# expansion_board.net
KiCad netlist of a schematic drawn in EAGLE
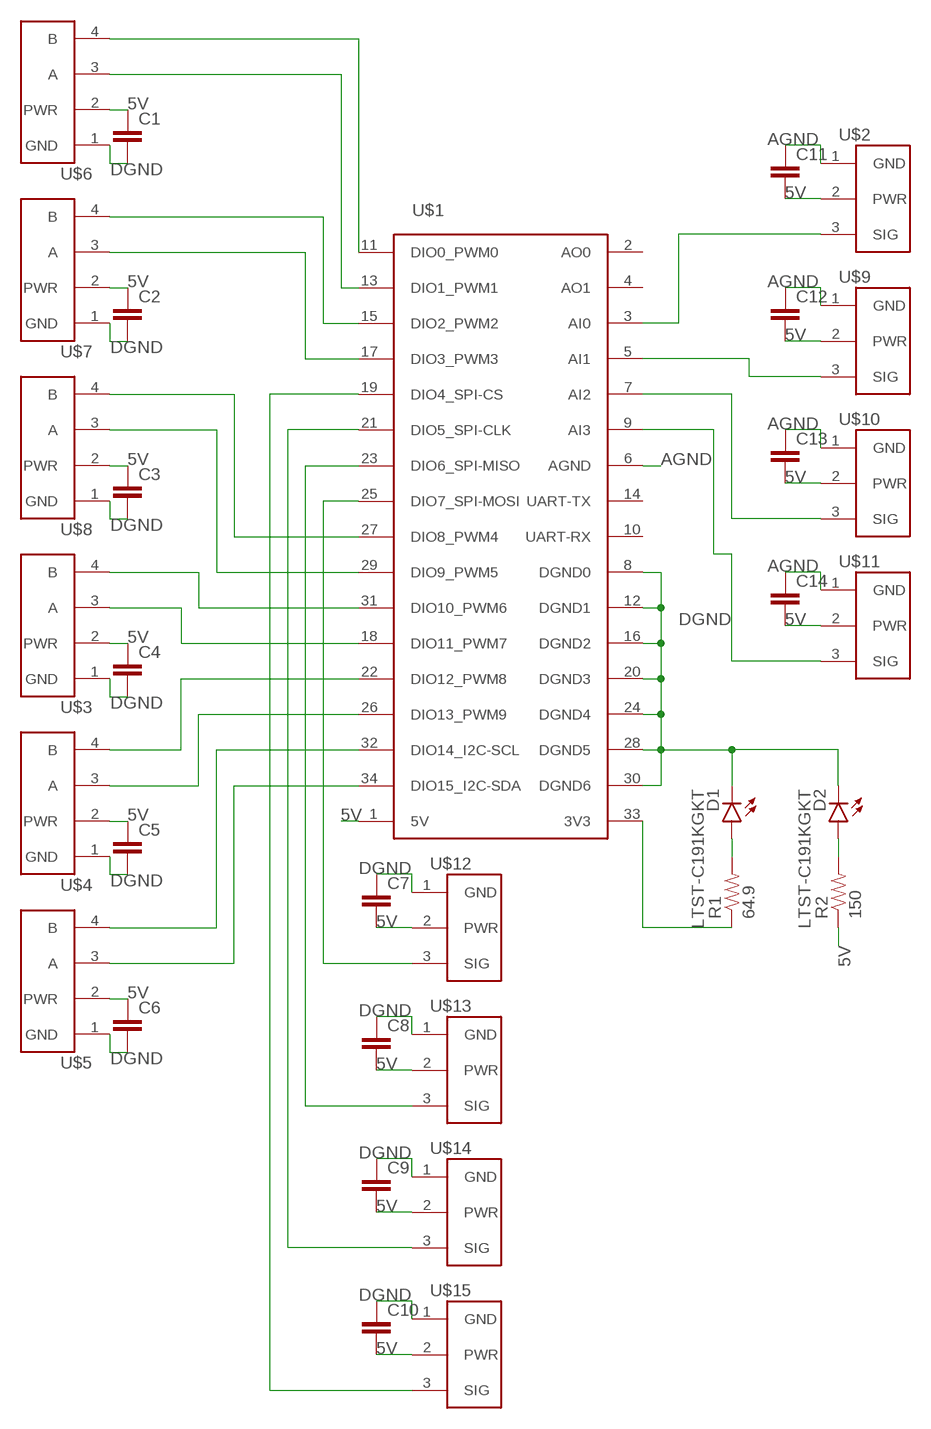
[diagram p0: schematic, sheet 1]

(export (version "E")
  (design (tool "Eeschema 10.0.6"))
  (components
    (comp (ref "C1")
      (value "CAP0603")
      (footprint "eagle-import:0603")
      (libsource (lib "eagle-import") (part "CAP0603"))
    )
    (comp (ref "C2")
      (value "CAP0603")
      (footprint "eagle-import:0603")
      (libsource (lib "eagle-import") (part "CAP0603"))
    )
    (comp (ref "C3")
      (value "CAP0603")
      (footprint "eagle-import:0603")
      (libsource (lib "eagle-import") (part "CAP0603"))
    )
    (comp (ref "C4")
      (value "CAP0603")
      (footprint "eagle-import:0603")
      (libsource (lib "eagle-import") (part "CAP0603"))
    )
    (comp (ref "C5")
      (value "CAP0603")
      (footprint "eagle-import:0603")
      (libsource (lib "eagle-import") (part "CAP0603"))
    )
    (comp (ref "C6")
      (value "CAP0603")
      (footprint "eagle-import:0603")
      (libsource (lib "eagle-import") (part "CAP0603"))
    )
    (comp (ref "C7")
      (value "CAP0603")
      (footprint "eagle-import:0603")
      (libsource (lib "eagle-import") (part "CAP0603"))
    )
    (comp (ref "C8")
      (value "CAP0603")
      (footprint "eagle-import:0603")
      (libsource (lib "eagle-import") (part "CAP0603"))
    )
    (comp (ref "C9")
      (value "CAP0603")
      (footprint "eagle-import:0603")
      (libsource (lib "eagle-import") (part "CAP0603"))
    )
    (comp (ref "C10")
      (value "CAP0603")
      (footprint "eagle-import:0603")
      (libsource (lib "eagle-import") (part "CAP0603"))
    )
    (comp (ref "C11")
      (value "CAP0603")
      (footprint "eagle-import:0603")
      (libsource (lib "eagle-import") (part "CAP0603"))
    )
    (comp (ref "C12")
      (value "CAP0603")
      (footprint "eagle-import:0603")
      (libsource (lib "eagle-import") (part "CAP0603"))
    )
    (comp (ref "C13")
      (value "CAP0603")
      (footprint "eagle-import:0603")
      (libsource (lib "eagle-import") (part "CAP0603"))
    )
    (comp (ref "C14")
      (value "CAP0603")
      (footprint "eagle-import:0603")
      (libsource (lib "eagle-import") (part "CAP0603"))
    )
    (comp (ref "D1")
      (value "LTST-C191KGKT")
      (footprint "eagle-import:LED-0603")
      (libsource (lib "eagle-import") (part "LED-GREEN0603"))
    )
    (comp (ref "D2")
      (value "LTST-C191KGKT")
      (footprint "eagle-import:LED-0603")
      (libsource (lib "eagle-import") (part "LED-GREEN0603"))
    )
    (comp (ref "R1")
      (value "64.9")
      (footprint "eagle-import:0603-RES")
      (libsource (lib "eagle-import") (part "RESISTOR0603-RES"))
    )
    (comp (ref "R2")
      (value "150")
      (footprint "eagle-import:0603-RES")
      (libsource (lib "eagle-import") (part "RESISTOR0603-RES"))
    )
    (comp (ref "U$1")
      (value "MXP")
      (footprint "eagle-import:SFH11-PBPC-D17-ST-BK")
      (libsource (lib "eagle-import") (part "MXP"))
    )
    (comp (ref "U$2")
      (value "22-23-2031")
      (footprint "eagle-import:22-23-2031")
      (libsource (lib "eagle-import") (part "22-23-2031"))
    )
    (comp (ref "U$3")
      (value "22-23-2041")
      (footprint "eagle-import:22-23-2041")
      (libsource (lib "eagle-import") (part "22-23-2041"))
    )
    (comp (ref "U$4")
      (value "22-23-2041")
      (footprint "eagle-import:22-23-2041")
      (libsource (lib "eagle-import") (part "22-23-2041"))
    )
    (comp (ref "U$5")
      (value "22-23-2041")
      (footprint "eagle-import:22-23-2041")
      (libsource (lib "eagle-import") (part "22-23-2041"))
    )
    (comp (ref "U$6")
      (value "22-23-2041")
      (footprint "eagle-import:22-23-2041")
      (libsource (lib "eagle-import") (part "22-23-2041"))
    )
    (comp (ref "U$7")
      (value "22-23-2041")
      (footprint "eagle-import:22-23-2041")
      (libsource (lib "eagle-import") (part "22-23-2041"))
    )
    (comp (ref "U$8")
      (value "22-23-2041")
      (footprint "eagle-import:22-23-2041")
      (libsource (lib "eagle-import") (part "22-23-2041"))
    )
    (comp (ref "U$9")
      (value "22-23-2031")
      (footprint "eagle-import:22-23-2031")
      (libsource (lib "eagle-import") (part "22-23-2031"))
    )
    (comp (ref "U$10")
      (value "22-23-2031")
      (footprint "eagle-import:22-23-2031")
      (libsource (lib "eagle-import") (part "22-23-2031"))
    )
    (comp (ref "U$11")
      (value "22-23-2031")
      (footprint "eagle-import:22-23-2031")
      (libsource (lib "eagle-import") (part "22-23-2031"))
    )
    (comp (ref "U$12")
      (value "22-23-2031")
      (footprint "eagle-import:22-23-2031")
      (libsource (lib "eagle-import") (part "22-23-2031"))
    )
    (comp (ref "U$13")
      (value "22-23-2031")
      (footprint "eagle-import:22-23-2031")
      (libsource (lib "eagle-import") (part "22-23-2031"))
    )
    (comp (ref "U$14")
      (value "22-23-2031")
      (footprint "eagle-import:22-23-2031")
      (libsource (lib "eagle-import") (part "22-23-2031"))
    )
    (comp (ref "U$15")
      (value "22-23-2031")
      (footprint "eagle-import:22-23-2031")
      (libsource (lib "eagle-import") (part "22-23-2031"))
    )
  )
  (nets
    (net (code "1") (name "/5V") (class "Default")
      (node (ref "C1") (pin "1") (pinfunction "1_1") (pintype "passive"))
      (node (ref "C10") (pin "2") (pinfunction "2_2") (pintype "passive"))
      (node (ref "C11") (pin "2") (pinfunction "2_2") (pintype "passive"))
      (node (ref "C12") (pin "2") (pinfunction "2_2") (pintype "passive"))
      (node (ref "C13") (pin "2") (pinfunction "2_2") (pintype "passive"))
      (node (ref "C14") (pin "2") (pinfunction "2_2") (pintype "passive"))
      (node (ref "C2") (pin "1") (pinfunction "1_1") (pintype "passive"))
      (node (ref "C3") (pin "1") (pinfunction "1_1") (pintype "passive"))
      (node (ref "C4") (pin "1") (pinfunction "1_1") (pintype "passive"))
      (node (ref "C5") (pin "1") (pinfunction "1_1") (pintype "passive"))
      (node (ref "C6") (pin "1") (pinfunction "1_1") (pintype "passive"))
      (node (ref "C7") (pin "2") (pinfunction "2_2") (pintype "passive"))
      (node (ref "C8") (pin "2") (pinfunction "2_2") (pintype "passive"))
      (node (ref "C9") (pin "2") (pinfunction "2_2") (pintype "passive"))
      (node (ref "R2") (pin "1") (pinfunction "1_1") (pintype "passive"))
      (node (ref "U$1") (pin "1") (pinfunction "5V_1") (pintype "power_in"))
      (node (ref "U$10") (pin "2") (pinfunction "PWR_2") (pintype "power_in"))
      (node (ref "U$11") (pin "2") (pinfunction "PWR_2") (pintype "power_in"))
      (node (ref "U$12") (pin "2") (pinfunction "PWR_2") (pintype "power_in"))
      (node (ref "U$13") (pin "2") (pinfunction "PWR_2") (pintype "power_in"))
      (node (ref "U$14") (pin "2") (pinfunction "PWR_2") (pintype "power_in"))
      (node (ref "U$15") (pin "2") (pinfunction "PWR_2") (pintype "power_in"))
      (node (ref "U$2") (pin "2") (pinfunction "PWR_2") (pintype "power_in"))
      (node (ref "U$3") (pin "2") (pinfunction "PWR_2") (pintype "power_in"))
      (node (ref "U$4") (pin "2") (pinfunction "PWR_2") (pintype "power_in"))
      (node (ref "U$5") (pin "2") (pinfunction "PWR_2") (pintype "power_in"))
      (node (ref "U$6") (pin "2") (pinfunction "PWR_2") (pintype "power_in"))
      (node (ref "U$7") (pin "2") (pinfunction "PWR_2") (pintype "power_in"))
      (node (ref "U$8") (pin "2") (pinfunction "PWR_2") (pintype "power_in"))
      (node (ref "U$9") (pin "2") (pinfunction "PWR_2") (pintype "power_in"))
    )
    (net (code "2") (name "/AGND") (class "Default")
      (node (ref "C11") (pin "1") (pinfunction "1_1") (pintype "passive"))
      (node (ref "C12") (pin "1") (pinfunction "1_1") (pintype "passive"))
      (node (ref "C13") (pin "1") (pinfunction "1_1") (pintype "passive"))
      (node (ref "C14") (pin "1") (pinfunction "1_1") (pintype "passive"))
      (node (ref "U$1") (pin "6") (pinfunction "AGND_6") (pintype "power_in"))
      (node (ref "U$10") (pin "1") (pinfunction "GND_1") (pintype "power_in"))
      (node (ref "U$11") (pin "1") (pinfunction "GND_1") (pintype "power_in"))
      (node (ref "U$2") (pin "1") (pinfunction "GND_1") (pintype "power_in"))
      (node (ref "U$9") (pin "1") (pinfunction "GND_1") (pintype "power_in"))
    )
    (net (code "3") (name "/DGND") (class "Default")
      (node (ref "C1") (pin "2") (pinfunction "2_2") (pintype "passive"))
      (node (ref "C10") (pin "1") (pinfunction "1_1") (pintype "passive"))
      (node (ref "C2") (pin "2") (pinfunction "2_2") (pintype "passive"))
      (node (ref "C3") (pin "2") (pinfunction "2_2") (pintype "passive"))
      (node (ref "C4") (pin "2") (pinfunction "2_2") (pintype "passive"))
      (node (ref "C5") (pin "2") (pinfunction "2_2") (pintype "passive"))
      (node (ref "C6") (pin "2") (pinfunction "2_2") (pintype "passive"))
      (node (ref "C7") (pin "1") (pinfunction "1_1") (pintype "passive"))
      (node (ref "C8") (pin "1") (pinfunction "1_1") (pintype "passive"))
      (node (ref "C9") (pin "1") (pinfunction "1_1") (pintype "passive"))
      (node (ref "D1") (pin "C") (pinfunction "C_C") (pintype "passive"))
      (node (ref "D2") (pin "C") (pinfunction "C_C") (pintype "passive"))
      (node (ref "U$1") (pin "12") (pinfunction "DGND1_12") (pintype "power_in"))
      (node (ref "U$1") (pin "16") (pinfunction "DGND2_16") (pintype "power_in"))
      (node (ref "U$1") (pin "20") (pinfunction "DGND3_20") (pintype "power_in"))
      (node (ref "U$1") (pin "24") (pinfunction "DGND4_24") (pintype "power_in"))
      (node (ref "U$1") (pin "28") (pinfunction "DGND5_28") (pintype "power_in"))
      (node (ref "U$1") (pin "30") (pinfunction "DGND6_30") (pintype "power_in"))
      (node (ref "U$1") (pin "8") (pinfunction "DGND0_8") (pintype "power_in"))
      (node (ref "U$12") (pin "1") (pinfunction "GND_1") (pintype "power_in"))
      (node (ref "U$13") (pin "1") (pinfunction "GND_1") (pintype "power_in"))
      (node (ref "U$14") (pin "1") (pinfunction "GND_1") (pintype "power_in"))
      (node (ref "U$15") (pin "1") (pinfunction "GND_1") (pintype "power_in"))
      (node (ref "U$3") (pin "1") (pinfunction "GND_1") (pintype "power_in"))
      (node (ref "U$4") (pin "1") (pinfunction "GND_1") (pintype "power_in"))
      (node (ref "U$5") (pin "1") (pinfunction "GND_1") (pintype "power_in"))
      (node (ref "U$6") (pin "1") (pinfunction "GND_1") (pintype "power_in"))
      (node (ref "U$7") (pin "1") (pinfunction "GND_1") (pintype "power_in"))
      (node (ref "U$8") (pin "1") (pinfunction "GND_1") (pintype "power_in"))
    )
    (net (code "4") (name "Net-(D1-PadA)") (class "Default")
      (node (ref "D1") (pin "A") (pinfunction "A_A") (pintype "passive"))
      (node (ref "R1") (pin "2") (pinfunction "2_2") (pintype "passive"))
    )
    (net (code "5") (name "Net-(D2-PadA)") (class "Default")
      (node (ref "D2") (pin "A") (pinfunction "A_A") (pintype "passive"))
      (node (ref "R2") (pin "2") (pinfunction "2_2") (pintype "passive"))
    )
    (net (code "6") (name "Net-(U$1-3V3)") (class "Default")
      (node (ref "R1") (pin "1") (pinfunction "1_1") (pintype "passive"))
      (node (ref "U$1") (pin "33") (pinfunction "3V3_33") (pintype "power_in"))
    )
    (net (code "7") (name "Net-(U$1-AI0)") (class "Default")
      (node (ref "U$1") (pin "3") (pinfunction "AI0_3") (pintype "input"))
      (node (ref "U$2") (pin "3") (pinfunction "SIG_3") (pintype "bidirectional"))
    )
    (net (code "8") (name "Net-(U$1-AI1)") (class "Default")
      (node (ref "U$1") (pin "5") (pinfunction "AI1_5") (pintype "input"))
      (node (ref "U$9") (pin "3") (pinfunction "SIG_3") (pintype "bidirectional"))
    )
    (net (code "9") (name "Net-(U$1-AI2)") (class "Default")
      (node (ref "U$1") (pin "7") (pinfunction "AI2_7") (pintype "input"))
      (node (ref "U$10") (pin "3") (pinfunction "SIG_3") (pintype "bidirectional"))
    )
    (net (code "10") (name "Net-(U$1-AI3)") (class "Default")
      (node (ref "U$1") (pin "9") (pinfunction "AI3_9") (pintype "input"))
      (node (ref "U$11") (pin "3") (pinfunction "SIG_3") (pintype "bidirectional"))
    )
    (net (code "11") (name "Net-(U$1-DIO0_PWM0)") (class "Default")
      (node (ref "U$1") (pin "11") (pinfunction "DIO0_PWM0_11") (pintype "bidirectional"))
      (node (ref "U$6") (pin "4") (pinfunction "B_4") (pintype "bidirectional"))
    )
    (net (code "12") (name "Net-(U$1-DIO1_PWM1)") (class "Default")
      (node (ref "U$1") (pin "13") (pinfunction "DIO1_PWM1_13") (pintype "bidirectional"))
      (node (ref "U$6") (pin "3") (pinfunction "A_3") (pintype "bidirectional"))
    )
    (net (code "13") (name "Net-(U$1-DIO2_PWM2)") (class "Default")
      (node (ref "U$1") (pin "15") (pinfunction "DIO2_PWM2_15") (pintype "bidirectional"))
      (node (ref "U$7") (pin "4") (pinfunction "B_4") (pintype "bidirectional"))
    )
    (net (code "14") (name "Net-(U$1-DIO3_PWM3)") (class "Default")
      (node (ref "U$1") (pin "17") (pinfunction "DIO3_PWM3_17") (pintype "bidirectional"))
      (node (ref "U$7") (pin "3") (pinfunction "A_3") (pintype "bidirectional"))
    )
    (net (code "15") (name "Net-(U$1-DIO4_SPI-CS)") (class "Default")
      (node (ref "U$1") (pin "19") (pinfunction "DIO4_SPI-CS_19") (pintype "bidirectional"))
      (node (ref "U$15") (pin "3") (pinfunction "SIG_3") (pintype "bidirectional"))
    )
    (net (code "16") (name "Net-(U$1-DIO5_SPI-CLK)") (class "Default")
      (node (ref "U$1") (pin "21") (pinfunction "DIO5_SPI-CLK_21") (pintype "bidirectional"))
      (node (ref "U$14") (pin "3") (pinfunction "SIG_3") (pintype "bidirectional"))
    )
    (net (code "17") (name "Net-(U$1-DIO6_SPI-MISO)") (class "Default")
      (node (ref "U$1") (pin "23") (pinfunction "DIO6_SPI-MISO_23") (pintype "bidirectional"))
      (node (ref "U$13") (pin "3") (pinfunction "SIG_3") (pintype "bidirectional"))
    )
    (net (code "18") (name "Net-(U$1-DIO7_SPI-MOSI)") (class "Default")
      (node (ref "U$1") (pin "25") (pinfunction "DIO7_SPI-MOSI_25") (pintype "bidirectional"))
      (node (ref "U$12") (pin "3") (pinfunction "SIG_3") (pintype "bidirectional"))
    )
    (net (code "19") (name "Net-(U$1-DIO8_PWM4)") (class "Default")
      (node (ref "U$1") (pin "27") (pinfunction "DIO8_PWM4_27") (pintype "bidirectional"))
      (node (ref "U$8") (pin "4") (pinfunction "B_4") (pintype "bidirectional"))
    )
    (net (code "20") (name "Net-(U$1-DIO9_PWM5)") (class "Default")
      (node (ref "U$1") (pin "29") (pinfunction "DIO9_PWM5_29") (pintype "bidirectional"))
      (node (ref "U$8") (pin "3") (pinfunction "A_3") (pintype "bidirectional"))
    )
    (net (code "21") (name "Net-(U$1-DIO10_PWM6)") (class "Default")
      (node (ref "U$1") (pin "31") (pinfunction "DIO10_PWM6_31") (pintype "bidirectional"))
      (node (ref "U$3") (pin "4") (pinfunction "B_4") (pintype "bidirectional"))
    )
    (net (code "22") (name "Net-(U$1-DIO11_PWM7)") (class "Default")
      (node (ref "U$1") (pin "18") (pinfunction "DIO11_PWM7_18") (pintype "bidirectional"))
      (node (ref "U$3") (pin "3") (pinfunction "A_3") (pintype "bidirectional"))
    )
    (net (code "23") (name "Net-(U$1-DIO12_PWM8)") (class "Default")
      (node (ref "U$1") (pin "22") (pinfunction "DIO12_PWM8_22") (pintype "bidirectional"))
      (node (ref "U$4") (pin "4") (pinfunction "B_4") (pintype "bidirectional"))
    )
    (net (code "24") (name "Net-(U$1-DIO13_PWM9)") (class "Default")
      (node (ref "U$1") (pin "26") (pinfunction "DIO13_PWM9_26") (pintype "bidirectional"))
      (node (ref "U$4") (pin "3") (pinfunction "A_3") (pintype "bidirectional"))
    )
    (net (code "25") (name "Net-(U$1-DIO14_I2C-SCL)") (class "Default")
      (node (ref "U$1") (pin "32") (pinfunction "DIO14_I2C-SCL_32") (pintype "bidirectional"))
      (node (ref "U$5") (pin "4") (pinfunction "B_4") (pintype "bidirectional"))
    )
    (net (code "26") (name "Net-(U$1-DIO15_I2C-SDA)") (class "Default")
      (node (ref "U$1") (pin "34") (pinfunction "DIO15_I2C-SDA_34") (pintype "bidirectional"))
      (node (ref "U$5") (pin "3") (pinfunction "A_3") (pintype "bidirectional"))
    )
    (net (code "27") (name "unconnected-(U$1-AO0-Pad2)") (class "Default")
      (node (ref "U$1") (pin "2") (pinfunction "AO0_2") (pintype "output"))
    )
    (net (code "28") (name "unconnected-(U$1-AO1-Pad4)") (class "Default")
      (node (ref "U$1") (pin "4") (pinfunction "AO1_4") (pintype "output"))
    )
    (net (code "29") (name "unconnected-(U$1-UART-RX-Pad10)") (class "Default")
      (node (ref "U$1") (pin "10") (pinfunction "UART-RX_10") (pintype "input"))
    )
    (net (code "30") (name "unconnected-(U$1-UART-TX-Pad14)") (class "Default")
      (node (ref "U$1") (pin "14") (pinfunction "UART-TX_14") (pintype "output"))
    )
  )
)
